# Casing.net
KiCad netlist of a schematic drawn in Altium Designer
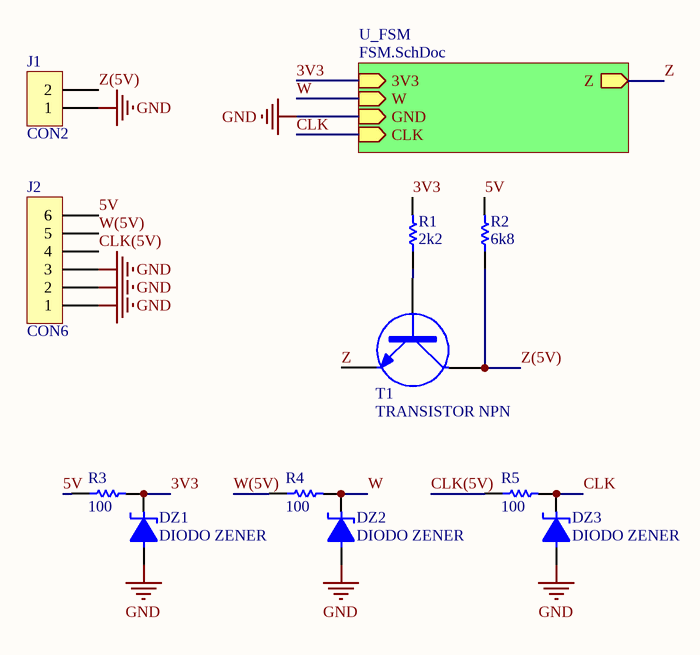
[diagram p0: Casing.SchDoc]

(export (version "E")
  (design (tool "Eeschema 10.0.6"))
  (components
    (comp (ref "DZ1")
      (value "DIODO ZENER")
      (footprint "DO41")
      (libsource (lib "LIBEBAL") (part "DIODO ZENER"))
    )
    (comp (ref "DZ2")
      (value "DIODO ZENER")
      (footprint "DO41")
      (libsource (lib "LIBEBAL") (part "DIODO ZENER"))
    )
    (comp (ref "DZ3")
      (value "DIODO ZENER")
      (footprint "DO41")
      (libsource (lib "LIBEBAL") (part "DIODO ZENER"))
    )
    (comp (ref "J1") (value "CON2") (footprint "SIP2") (libsource (lib "LIBEBAL") (part "CON2")))
    (comp (ref "J2") (value "CON6") (footprint "SIP6") (libsource (lib "LIBEBAL") (part "CON6")))
    (comp (ref "R1") (value "2k2") (footprint "0805") (libsource (lib "LIB PIO IX") (part "RES")))
    (comp (ref "R2") (value "6k8") (footprint "0805") (libsource (lib "LIB PIO IX") (part "RES")))
    (comp (ref "R3") (value "100") (footprint "0805") (libsource (lib "LIB PIO IX") (part "RES")))
    (comp (ref "R4") (value "100") (footprint "0805") (libsource (lib "LIB PIO IX") (part "RES")))
    (comp (ref "R5") (value "100") (footprint "0805") (libsource (lib "LIB PIO IX") (part "RES")))
    (comp (ref "T1")
      (value "TRANSISTOR NPN")
      (footprint "TO92")
      (libsource (lib "LIBEBAL") (part "TRANSISTOR NPN"))
    )
  )
  (nets
    (net (code "1") (name "/3V3") (class "Default")
      (node (ref "DZ1") (pin "2") (pinfunction "2_2") (pintype "passive"))
      (node (ref "R1") (pin "2") (pinfunction "2_2") (pintype "passive"))
      (node (ref "R3") (pin "2") (pinfunction "2_2") (pintype "passive"))
    )
    (net (code "2") (name "/5V") (class "Default")
      (node (ref "J2") (pin "6") (pinfunction "6_6") (pintype "passive"))
      (node (ref "R2") (pin "2") (pinfunction "2_2") (pintype "passive"))
      (node (ref "R3") (pin "1") (pinfunction "1_1") (pintype "passive"))
    )
    (net (code "3") (name "/CLK") (class "Default")
      (node (ref "DZ3") (pin "2") (pinfunction "2_2") (pintype "passive"))
      (node (ref "R5") (pin "2") (pinfunction "2_2") (pintype "passive"))
    )
    (net (code "4") (name "/CLK(5V)") (class "Default")
      (node (ref "J2") (pin "4") (pinfunction "4_4") (pintype "passive"))
      (node (ref "R5") (pin "1") (pinfunction "1_1") (pintype "passive"))
    )
    (net (code "5") (name "/W") (class "Default")
      (node (ref "DZ2") (pin "2") (pinfunction "2_2") (pintype "passive"))
      (node (ref "R4") (pin "2") (pinfunction "2_2") (pintype "passive"))
    )
    (net (code "6") (name "/W(5V)") (class "Default")
      (node (ref "J2") (pin "5") (pinfunction "5_5") (pintype "passive"))
      (node (ref "R4") (pin "1") (pinfunction "1_1") (pintype "passive"))
    )
    (net (code "7") (name "/Z") (class "Default")
      (node (ref "T1") (pin "3") (pinfunction "E_3") (pintype "passive"))
    )
    (net (code "8") (name "/Z(5V)") (class "Default")
      (node (ref "J1") (pin "2") (pinfunction "2_2") (pintype "passive"))
      (node (ref "R2") (pin "1") (pinfunction "1_1") (pintype "passive"))
      (node (ref "T1") (pin "2") (pinfunction "C_2") (pintype "passive"))
    )
    (net (code "9") (name "GND") (class "Default")
      (node (ref "DZ1") (pin "1") (pinfunction "1_1") (pintype "passive"))
      (node (ref "DZ2") (pin "1") (pinfunction "1_1") (pintype "passive"))
      (node (ref "DZ3") (pin "1") (pinfunction "1_1") (pintype "passive"))
      (node (ref "J1") (pin "1") (pinfunction "1_1") (pintype "passive"))
      (node (ref "J2") (pin "1") (pinfunction "1_1") (pintype "passive"))
      (node (ref "J2") (pin "2") (pinfunction "2_2") (pintype "passive"))
      (node (ref "J2") (pin "3") (pinfunction "3_3") (pintype "passive"))
    )
    (net (code "10") (name "Net-(T1-B)") (class "Default")
      (node (ref "R1") (pin "1") (pinfunction "1_1") (pintype "passive"))
      (node (ref "T1") (pin "1") (pinfunction "B_1") (pintype "passive"))
    )
  )
)
